# thermo.net
KiCad netlist of a schematic drawn in EAGLE
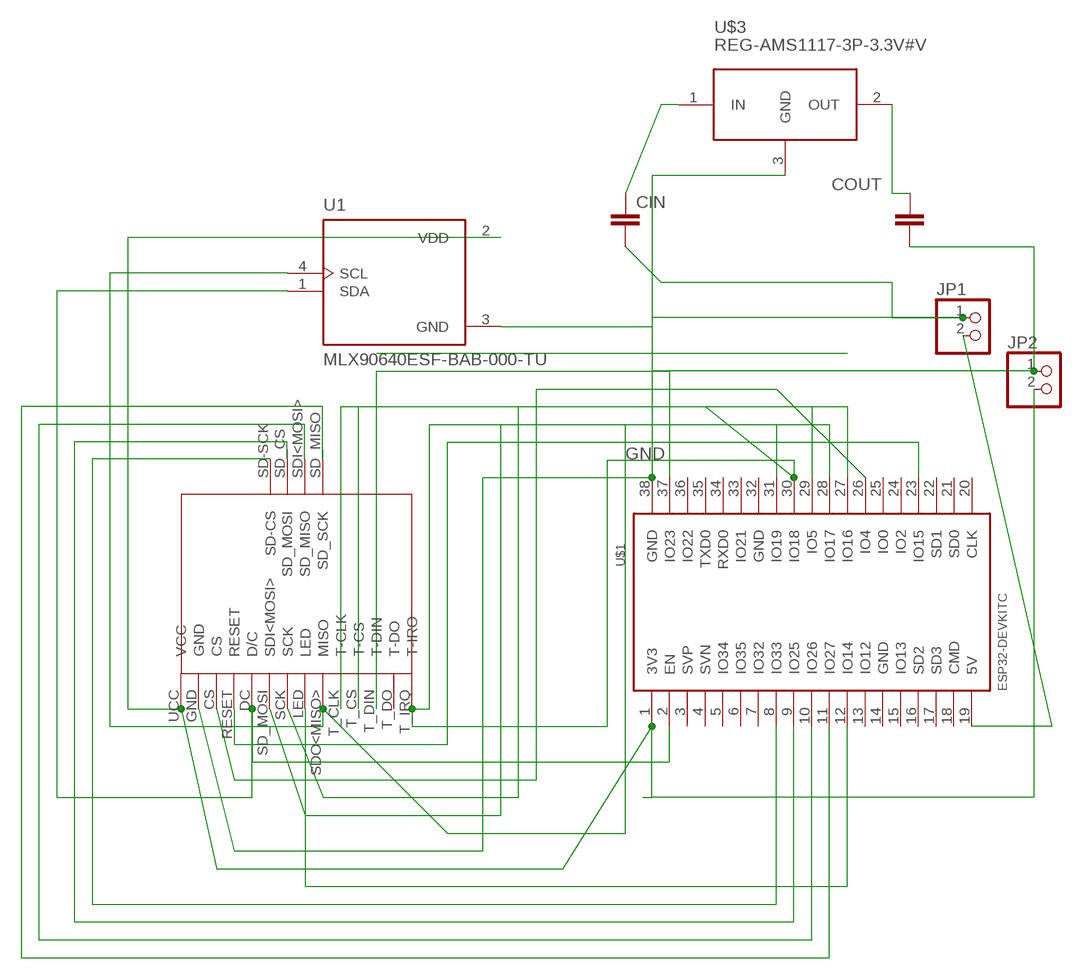
[diagram p0: schematic, sheet 1]

(export (version "E")
  (design (tool "Eeschema 10.0.6"))
  (components
    (comp (ref "CIN")
      (value "C2.5/2")
      (footprint "eagle-import:C2.5-2")
      (libsource (lib "eagle-import") (part "C2.5/2"))
    )
    (comp (ref "COUT")
      (value "C2.5/2")
      (footprint "eagle-import:C2.5-2")
      (libsource (lib "eagle-import") (part "C2.5/2"))
    )
    (comp (ref "JP1")
      (value "PINHD-1X2")
      (footprint "eagle-import:1X02")
      (libsource (lib "eagle-import") (part "PINHD-1X2"))
    )
    (comp (ref "JP2")
      (value "PINHD-1X2")
      (footprint "eagle-import:1X02")
      (libsource (lib "eagle-import") (part "PINHD-1X2"))
    )
    (comp (ref "U$1")
      (value "ESP32DEVKITC")
      (footprint "eagle-import:ESP32-DEVKITC")
      (libsource (lib "eagle-import") (part "ESP32DEVKITC"))
    )
    (comp (ref "U$2")
      (value "TFT.SPI.240X320")
      (footprint "eagle-import:SKR1")
      (libsource (lib "eagle-import") (part "TFT.SPI.240X320"))
    )
    (comp (ref "U$3")
      (value "REG-AMS1117-3P-3.3V#V")
      (footprint "eagle-import:REG-AMS1117-3P#V")
      (libsource (lib "eagle-import") (part "REG-AMS1117-3P-#V3.3V"))
    )
    (comp (ref "U1")
      (value "MLX90640ESF-BAB-000-TU")
      (footprint "eagle-import:TO292P945H1165-4")
      (fields (field (name "MF") "Melexis Technologies NV"))
      (libsource (lib "eagle-import") (part "MLX90640ESF-BAB-000-TU"))
    )
  )
  (nets
    (net (code "1") (name "/GND") (class "Default")
      (node (ref "CIN") (pin "2") (pinfunction "2_2") (pintype "passive"))
      (node (ref "COUT") (pin "2") (pinfunction "2_2") (pintype "passive"))
      (node (ref "JP1") (pin "1") (pinfunction "1_1") (pintype "passive"))
      (node (ref "JP2") (pin "1") (pinfunction "1_1") (pintype "passive"))
      (node (ref "U$1") (pin "38") (pinfunction "GND_38") (pintype "bidirectional"))
      (node (ref "U$2") (pin "GND") (pinfunction "GND_GND") (pintype "bidirectional"))
      (node (ref "U$3") (pin "3") (pinfunction "GND_3") (pintype "bidirectional"))
      (node (ref "U1") (pin "3") (pinfunction "GND_3") (pintype "power_in"))
    )
    (net (code "2") (name "Net-(U$1-3V3)") (class "Default")
      (node (ref "JP2") (pin "2") (pinfunction "2_2") (pintype "passive"))
      (node (ref "U$1") (pin "1") (pinfunction "3V3_1") (pintype "bidirectional"))
      (node (ref "U$2") (pin "UCC") (pinfunction "VCC_UCC") (pintype "bidirectional"))
      (node (ref "U1") (pin "2") (pinfunction "VDD_2") (pintype "power_in"))
    )
    (net (code "3") (name "Net-(U$1-5V)") (class "Default")
      (node (ref "JP1") (pin "2") (pinfunction "2_2") (pintype "passive"))
      (node (ref "U$1") (pin "19") (pinfunction "5V_19") (pintype "bidirectional"))
    )
    (net (code "4") (name "Net-(U$1-EN)") (class "Default")
      (node (ref "U$1") (pin "2") (pinfunction "EN_2") (pintype "bidirectional"))
      (node (ref "U$2") (pin "DC") (pinfunction "D/C_DC") (pintype "bidirectional"))
      (node (ref "U1") (pin "1") (pinfunction "SDA_1") (pintype "bidirectional"))
    )
    (net (code "5") (name "Net-(U$1-IO4)") (class "Default")
      (node (ref "U$1") (pin "26") (pinfunction "IO4_26") (pintype "bidirectional"))
      (node (ref "U$2") (pin "CS") (pinfunction "CS_CS") (pintype "bidirectional"))
    )
    (net (code "6") (name "Net-(U$1-IO14)") (class "Default")
      (node (ref "U$1") (pin "12") (pinfunction "IO14_12") (pintype "bidirectional"))
      (node (ref "U$2") (pin "LED") (pinfunction "LED_LED") (pintype "bidirectional"))
    )
    (net (code "7") (name "Net-(U$1-IO15)") (class "Default")
      (node (ref "U$1") (pin "23") (pinfunction "IO15_23") (pintype "bidirectional"))
      (node (ref "U$2") (pin "RESET") (pinfunction "RESET_RESET") (pintype "bidirectional"))
    )
    (net (code "8") (name "Net-(U$1-IO16)") (class "Default")
      (node (ref "U$1") (pin "27") (pinfunction "IO16_27") (pintype "bidirectional"))
      (node (ref "U$1") (pin "29") (pinfunction "IO5_29") (pintype "bidirectional"))
      (node (ref "U$2") (pin "T_CLK") (pinfunction "T-CLK_T_CLK") (pintype "bidirectional"))
      (node (ref "U$2") (pin "T_CS") (pinfunction "T-CS_T_CS") (pintype "bidirectional"))
    )
    (net (code "9") (name "Net-(U$1-IO17)") (class "Default")
      (node (ref "U$1") (pin "28") (pinfunction "IO17_28") (pintype "bidirectional"))
      (node (ref "U$1") (pin "30") (pinfunction "IO18_30") (pintype "bidirectional"))
      (node (ref "U$2") (pin "SCK") (pinfunction "SCK_SCK") (pintype "bidirectional"))
      (node (ref "U$2") (pin "T_IRQ") (pinfunction "T-IRO_T_IRQ") (pintype "bidirectional"))
    )
    (net (code "10") (name "Net-(U$1-IO19)") (class "Default")
      (node (ref "U$1") (pin "31") (pinfunction "IO19_31") (pintype "bidirectional"))
      (node (ref "U$2") (pin "SDO<MISO>") (pinfunction "MISO_SDO<MISO>") (pintype "bidirectional"))
      (node (ref "U1") (pin "4") (pinfunction "SCL_4") (pintype "input"))
    )
    (net (code "11") (name "Net-(U$1-IO23)") (class "Default")
      (node (ref "U$1") (pin "37") (pinfunction "IO23_37") (pintype "bidirectional"))
      (node (ref "U$2") (pin "T_DIN") (pinfunction "T-DIN_T_DIN") (pintype "bidirectional"))
    )
    (net (code "12") (name "Net-(U$1-IO25)") (class "Default")
      (node (ref "U$1") (pin "9") (pinfunction "IO25_9") (pintype "bidirectional"))
      (node (ref "U$2") (pin "SD_CS") (pinfunction "SD_MOSI_SD_CS") (pintype "bidirectional"))
    )
    (net (code "13") (name "Net-(U$1-IO26)") (class "Default")
      (node (ref "U$1") (pin "10") (pinfunction "IO26_10") (pintype "bidirectional"))
      (node (ref "U$2") (pin "SDI<MOSI>") (pinfunction "SD_MISO_SDI<MOSI>") (pintype "bidirectional"))
    )
    (net (code "14") (name "Net-(U$1-IO27)") (class "Default")
      (node (ref "U$1") (pin "11") (pinfunction "IO27_11") (pintype "bidirectional"))
      (node (ref "U$2") (pin "SD_MISO") (pinfunction "SD_SCK_SD_MISO") (pintype "bidirectional"))
    )
    (net (code "15") (name "Net-(U$1-IO33)") (class "Default")
      (node (ref "U$1") (pin "8") (pinfunction "IO33_8") (pintype "bidirectional"))
      (node (ref "U$2") (pin "SD-SCK") (pinfunction "SD-CS_SD-SCK") (pintype "bidirectional"))
    )
    (net (code "16") (name "Net-(U$3-IN)") (class "Default")
      (node (ref "CIN") (pin "1") (pinfunction "1_1") (pintype "passive"))
      (node (ref "U$3") (pin "1") (pinfunction "IN_1") (pintype "bidirectional"))
    )
    (net (code "17") (name "Net-(U$3-OUT)") (class "Default")
      (node (ref "COUT") (pin "1") (pinfunction "1_1") (pintype "passive"))
      (node (ref "U$3") (pin "2") (pinfunction "OUT_2") (pintype "bidirectional"))
    )
    (net (code "18") (name "unconnected-(U$1-CLK-Pad20)") (class "Default")
      (node (ref "U$1") (pin "20") (pinfunction "CLK_20") (pintype "bidirectional"))
    )
    (net (code "19") (name "unconnected-(U$1-CMD-Pad18)") (class "Default")
      (node (ref "U$1") (pin "18") (pinfunction "CMD_18") (pintype "bidirectional"))
    )
    (net (code "20") (name "unconnected-(U$1-GND-Pad14)") (class "Default")
      (node (ref "U$1") (pin "14") (pinfunction "GND_14") (pintype "bidirectional"))
    )
    (net (code "21") (name "unconnected-(U$1-GND-Pad32)") (class "Default")
      (node (ref "U$1") (pin "32") (pinfunction "GND_32") (pintype "bidirectional"))
    )
    (net (code "22") (name "unconnected-(U$1-IO0-Pad25)") (class "Default")
      (node (ref "U$1") (pin "25") (pinfunction "IO0_25") (pintype "bidirectional"))
    )
    (net (code "23") (name "unconnected-(U$1-IO2-Pad24)") (class "Default")
      (node (ref "U$1") (pin "24") (pinfunction "IO2_24") (pintype "bidirectional"))
    )
    (net (code "24") (name "unconnected-(U$1-IO12-Pad13)") (class "Default")
      (node (ref "U$1") (pin "13") (pinfunction "IO12_13") (pintype "bidirectional"))
    )
    (net (code "25") (name "unconnected-(U$1-IO13-Pad15)") (class "Default")
      (node (ref "U$1") (pin "15") (pinfunction "IO13_15") (pintype "bidirectional"))
    )
    (net (code "26") (name "unconnected-(U$1-IO21-Pad33)") (class "Default")
      (node (ref "U$1") (pin "33") (pinfunction "IO21_33") (pintype "bidirectional"))
    )
    (net (code "27") (name "unconnected-(U$1-IO22-Pad36)") (class "Default")
      (node (ref "U$1") (pin "36") (pinfunction "IO22_36") (pintype "bidirectional"))
    )
    (net (code "28") (name "unconnected-(U$1-IO32-Pad7)") (class "Default")
      (node (ref "U$1") (pin "7") (pinfunction "IO32_7") (pintype "bidirectional"))
    )
    (net (code "29") (name "unconnected-(U$1-IO34-Pad5)") (class "Default")
      (node (ref "U$1") (pin "5") (pinfunction "IO34_5") (pintype "bidirectional"))
    )
    (net (code "30") (name "unconnected-(U$1-IO35-Pad6)") (class "Default")
      (node (ref "U$1") (pin "6") (pinfunction "IO35_6") (pintype "bidirectional"))
    )
    (net (code "31") (name "unconnected-(U$1-RXD0-Pad34)") (class "Default")
      (node (ref "U$1") (pin "34") (pinfunction "RXD0_34") (pintype "bidirectional"))
    )
    (net (code "32") (name "unconnected-(U$1-SD0-Pad21)") (class "Default")
      (node (ref "U$1") (pin "21") (pinfunction "SD0_21") (pintype "bidirectional"))
    )
    (net (code "33") (name "unconnected-(U$1-SD1-Pad22)") (class "Default")
      (node (ref "U$1") (pin "22") (pinfunction "SD1_22") (pintype "bidirectional"))
    )
    (net (code "34") (name "unconnected-(U$1-SD2-Pad16)") (class "Default")
      (node (ref "U$1") (pin "16") (pinfunction "SD2_16") (pintype "bidirectional"))
    )
    (net (code "35") (name "unconnected-(U$1-SD3-Pad17)") (class "Default")
      (node (ref "U$1") (pin "17") (pinfunction "SD3_17") (pintype "bidirectional"))
    )
    (net (code "36") (name "unconnected-(U$1-SVN-Pad4)") (class "Default")
      (node (ref "U$1") (pin "4") (pinfunction "SVN_4") (pintype "bidirectional"))
    )
    (net (code "37") (name "unconnected-(U$1-SVP-Pad3)") (class "Default")
      (node (ref "U$1") (pin "3") (pinfunction "SVP_3") (pintype "bidirectional"))
    )
    (net (code "38") (name "unconnected-(U$1-TXD0-Pad35)") (class "Default")
      (node (ref "U$1") (pin "35") (pinfunction "TXD0_35") (pintype "bidirectional"))
    )
    (net (code "39") (name "unconnected-(U$2-SDI<MOSI>-PadSD_MOSI)") (class "Default")
      (node (ref "U$2") (pin "SD_MOSI") (pinfunction "SDI<MOSI>_SD_MOSI") (pintype "bidirectional"))
    )
    (net (code "40") (name "unconnected-(U$2-T-DO-PadT_DO)") (class "Default")
      (node (ref "U$2") (pin "T_DO") (pinfunction "T-DO_T_DO") (pintype "bidirectional"))
    )
  )
)
